# BUCK_Module_2596_ADJ.net
KiCad netlist of a schematic drawn in Altium Designer
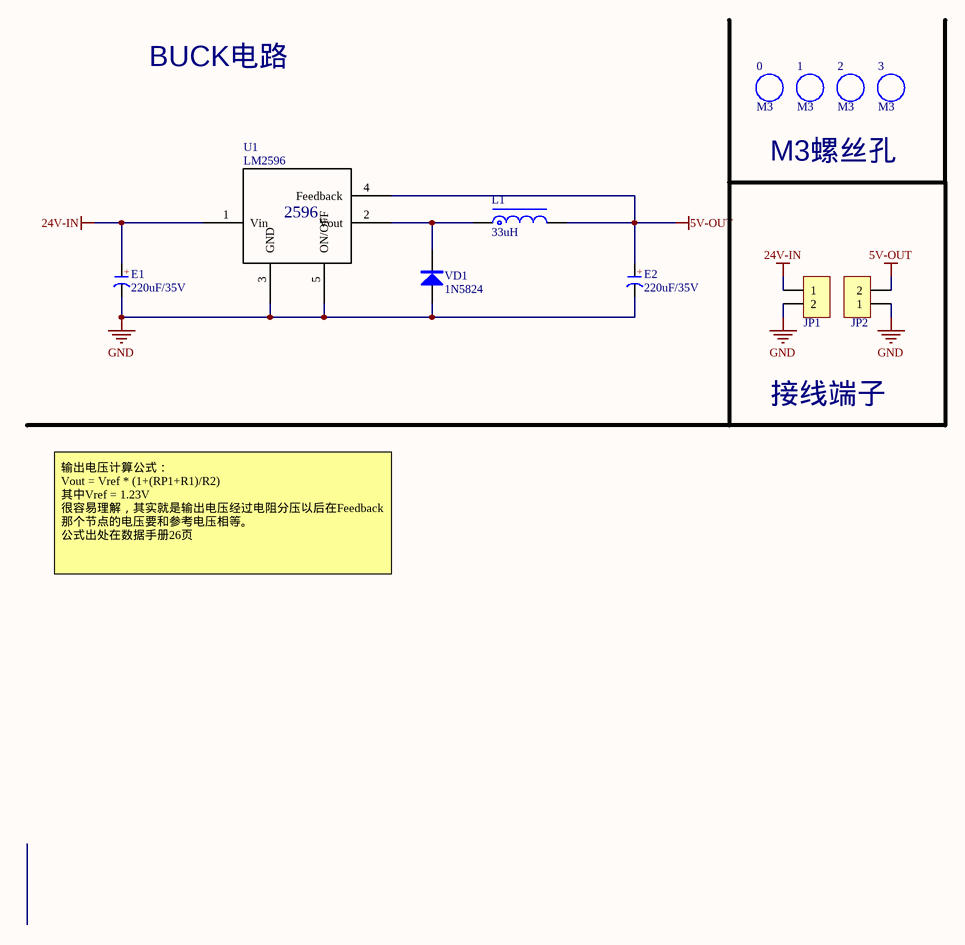
[diagram p0: BUCK_Module_2596_ADJ.SchDoc]

(export (version "E")
  (design (tool "Eeschema 10.0.6"))
  (components
    (comp (ref "0")
      (value "M3")
      (footprint "M3 125X200")
      (description "铜柱孔")
      (fields (field (name "版权归属") "源创客"))
      (libsource (lib "未分类器件") (part "M3"))
    )
    (comp (ref "1")
      (value "M3")
      (footprint "M3 125X200")
      (description "铜柱孔")
      (fields (field (name "版权归属") "源创客"))
      (libsource (lib "未分类器件") (part "M3"))
    )
    (comp (ref "2")
      (value "M3")
      (footprint "M3 125X200")
      (description "铜柱孔")
      (fields (field (name "版权归属") "源创客"))
      (libsource (lib "未分类器件") (part "M3"))
    )
    (comp (ref "3")
      (value "M3")
      (footprint "M3 125X200")
      (description "铜柱孔")
      (fields (field (name "版权归属") "源创客"))
      (libsource (lib "未分类器件") (part "M3"))
    )
    (comp (ref "E1")
      (value "220uF/35V")
      (footprint "CM D(6.3*5.4)")
      (description "贴片电解电容")
      (fields (field (name "版权归属") "源创客"))
      (libsource (lib "电阻-电容-电感") (part "C-CM"))
    )
    (comp (ref "E2")
      (value "220uF/35V")
      (footprint "CM D(6.3*7.7)")
      (description "贴片电解电容")
      (fields (field (name "版权归属") "源创客"))
      (libsource (lib "电阻-电容-电感") (part "C-CM"))
    )
    (comp (ref "JP1")
      (value "HDR-1X2")
      (footprint "KF301-2P")
      (description "2P接插件")
      (fields (field (name "版权归属") "源创客"))
      (libsource (lib "") (part "Header 2_1"))
    )
    (comp (ref "JP2")
      (value "HDR-1X2")
      (footprint "KF301-2P")
      (description "2P接插件")
      (fields (field (name "版权归属") "源创客"))
      (libsource (lib "接插件") (part "Header 2"))
    )
    (comp (ref "L1")
      (value "33uH")
      (footprint "CDRH127")
      (description "功率屏蔽电感")
      (fields (field (name "版权归属") "源创客"))
      (libsource (lib "电阻-电容-电感") (part "L-CDRH"))
    )
    (comp (ref "U1")
      (value "LM2596")
      (footprint "LM2596")
      (libsource (lib "Multicoloredstone's_IC_Lib") (part "LM2596"))
    )
    (comp (ref "VD1")
      (value "1N5824")
      (footprint "SMB")
      (description "肖特基二极管")
      (fields (field (name "版权归属") "源创客"))
      (libsource (lib "二极管-整流桥") (part "SS24"))
    )
  )
  (nets
    (net (code "1") (name "5V-OUT") (class "Default")
      (node (ref "E2") (pin "1") (pinfunction "A_1") (pintype "passive"))
      (node (ref "JP2") (pin "2") (pinfunction "2_2") (pintype "passive"))
      (node (ref "L1") (pin "2") (pinfunction "2_2") (pintype "passive"))
      (node (ref "U1") (pin "4") (pinfunction "Feedback_4") (pintype "passive"))
    )
    (net (code "2") (name "24V-IN") (class "Default")
      (node (ref "E1") (pin "1") (pinfunction "A_1") (pintype "passive"))
      (node (ref "JP1") (pin "1") (pinfunction "1_1") (pintype "passive"))
      (node (ref "U1") (pin "1") (pinfunction "Vin_1") (pintype "passive"))
    )
    (net (code "3") (name "GND") (class "Default")
      (node (ref "E1") (pin "2") (pinfunction "K_2") (pintype "passive"))
      (node (ref "E2") (pin "2") (pinfunction "K_2") (pintype "passive"))
      (node (ref "JP1") (pin "2") (pinfunction "2_2") (pintype "passive"))
      (node (ref "JP2") (pin "1") (pinfunction "1_1") (pintype "passive"))
      (node (ref "U1") (pin "3") (pinfunction "GND_3") (pintype "passive"))
      (node (ref "U1") (pin "5") (pinfunction "ON/OFF_5") (pintype "passive"))
      (node (ref "VD1") (pin "1") (pinfunction "A_1") (pintype "passive"))
    )
    (net (code "4") (name "Net-(U1-Vout)") (class "Default")
      (node (ref "L1") (pin "1") (pinfunction "1_1") (pintype "passive"))
      (node (ref "U1") (pin "2") (pinfunction "Vout_2") (pintype "passive"))
      (node (ref "VD1") (pin "2") (pinfunction "K_2") (pintype "passive"))
    )
  )
)
